# GPS.net
KiCad netlist of a schematic drawn in Altium Designer
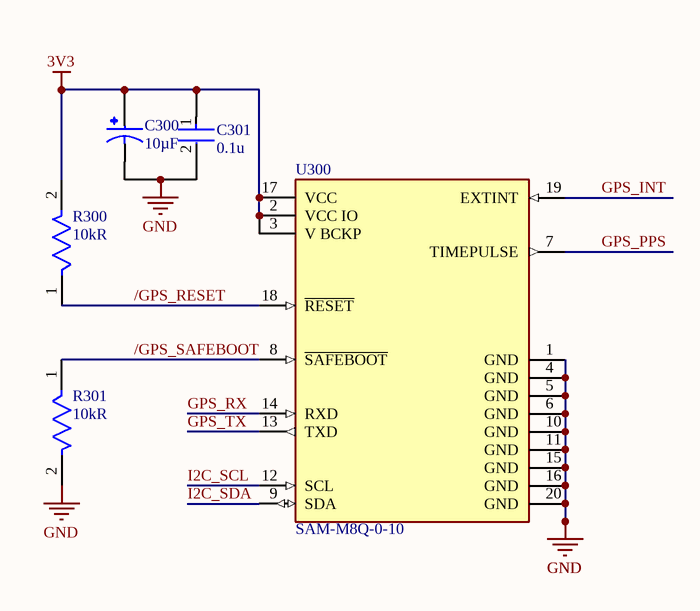
[diagram p0: GPS.SchDoc]

(export (version "E")
  (design (tool "Eeschema 10.0.6"))
  (components
    (comp (ref "C300")
      (value "10µF")
      (footprint "CAP_EEEFN1C100R")
      (description "10ÂµF 16V Aluminum Electrolytic Capacitors Radial, Can - SMD 1.35Ohm @ 100kHz 2000 Hrs @ 105Â°C")
      (fields (field (name "DIGI-KEY_PART_NUMBER") "10-EEE-FN1C100RCT-ND") (field (name "MP") "EEEFN1C100R"))
      (libsource (lib "Erich Robb") (part "EEEFN1C100R"))
    )
    (comp (ref "C301")
      (value "CL10C681JB8NFNC")
      (footprint "FP-CL10-IPC_A")
      (description "Cap Ceramic 680pF 50V C0G ±5% Pad SMD 0603 +125°C T/R")
      (fields (field (name "CAPACITANCE") "0.1u") (field (name "TOLERANCE") "5%"))
      (libsource (lib "Altium Content Vault") (part "b4654b650e69147ec39a6b967a45e02"))
    )
    (comp (ref "R300")
      (value "10kR")
      (footprint "FP-CPF0603-MFG")
      (description "RES SMD 2.15KΩ 0.1% 1/16W 0603")
      (fields
        (field (name "MANUFACTURER") "TE Connectivity")
        (field (name "OCTOPART") "https://octopart.com/cpf0603b2k15e1-te+connectivity-22739551")
      )
      (libsource (lib "Altium Content Vault") (part "1029c3af85768c4190bb7ad29bc67b5"))
    )
    (comp (ref "R301")
      (value "10kR")
      (footprint "FP-CPF0603-MFG")
      (description "RES SMD 2.15KΩ 0.1% 1/16W 0603")
      (fields
        (field (name "MANUFACTURER") "TE Connectivity")
        (field (name "OCTOPART") "https://octopart.com/cpf0603b2k15e1-te+connectivity-22739551")
      )
      (libsource (lib "Altium Content Vault") (part "1029c3af85768c4190bb7ad29bc67b5"))
    )
    (comp (ref "U300")
      (value "SAM-M8Q-0-10")
      (footprint "FP-SAM-M8Q-0-10-MFG")
      (description "RF RX GALILEO 1.575GHZ/1.602GHZ")
      (fields
        (field (name "MANUFACTURER") "uBlox")
        (field (name "OCTOPART") "https://octopart.com/sam-m8q-0-10-u-blox-88247750")
      )
      (libsource (lib "Altium Content Vault") (part "e897669bc61729ed63f6e62e0b1e840"))
    )
  )
  (nets
    (net (code "1") (name "/GPS_INT") (class "Default")
      (node (ref "U300") (pin "19") (pinfunction "EXTINT_19") (pintype "input"))
    )
    (net (code "2") (name "/GPS_PPS") (class "Default")
      (node (ref "U300") (pin "7") (pinfunction "TIMEPULSE_7") (pintype "output"))
    )
    (net (code "3") (name "/GPS_RX") (class "Default")
      (node (ref "U300") (pin "14") (pinfunction "RXD_14") (pintype "input"))
    )
    (net (code "4") (name "/GPS_TX") (class "Default")
      (node (ref "U300") (pin "13") (pinfunction "TXD_13") (pintype "output"))
    )
    (net (code "5") (name "/I2C_SCL") (class "Default")
      (node (ref "U300") (pin "12") (pinfunction "SCL_12") (pintype "input"))
    )
    (net (code "6") (name "/I2C_SDA") (class "Default")
      (node (ref "U300") (pin "9") (pinfunction "SDA_9") (pintype "bidirectional"))
    )
    (net (code "7") (name "/{slash}GPS_RESET") (class "Default")
      (node (ref "R300") (pin "1") (pinfunction "1_1") (pintype "passive"))
      (node (ref "U300") (pin "18") (pinfunction "~{RESET}_18") (pintype "input"))
    )
    (net (code "8") (name "/{slash}GPS_SAFEBOOT") (class "Default")
      (node (ref "R301") (pin "1") (pinfunction "1_1") (pintype "passive"))
      (node (ref "U300") (pin "8") (pinfunction "~{SAFEBOOT}_8") (pintype "input"))
    )
    (net (code "9") (name "3V3") (class "Default")
      (node (ref "C300") (pin "1") (pinfunction "1_1") (pintype "passive"))
      (node (ref "C301") (pin "1") (pinfunction "1_1") (pintype "passive"))
      (node (ref "R300") (pin "2") (pinfunction "2_2") (pintype "passive"))
      (node (ref "U300") (pin "17") (pinfunction "VCC_17") (pintype "power_in"))
      (node (ref "U300") (pin "2") (pinfunction "VCC_IO_2") (pintype "power_in"))
      (node (ref "U300") (pin "3") (pinfunction "V_BCKP_3") (pintype "power_in"))
    )
    (net (code "10") (name "GND") (class "Default")
      (node (ref "C300") (pin "2") (pinfunction "2_2") (pintype "passive"))
      (node (ref "C301") (pin "2") (pinfunction "2_2") (pintype "passive"))
      (node (ref "R301") (pin "2") (pinfunction "2_2") (pintype "passive"))
      (node (ref "U300") (pin "1") (pinfunction "GND_1") (pintype "power_in"))
      (node (ref "U300") (pin "10") (pinfunction "GND_10") (pintype "power_in"))
      (node (ref "U300") (pin "11") (pinfunction "GND_11") (pintype "power_in"))
      (node (ref "U300") (pin "15") (pinfunction "GND_15") (pintype "power_in"))
      (node (ref "U300") (pin "16") (pinfunction "GND_16") (pintype "power_in"))
      (node (ref "U300") (pin "20") (pinfunction "GND_20") (pintype "power_in"))
      (node (ref "U300") (pin "4") (pinfunction "GND_4") (pintype "power_in"))
      (node (ref "U300") (pin "5") (pinfunction "GND_5") (pintype "power_in"))
      (node (ref "U300") (pin "6") (pinfunction "GND_6") (pintype "power_in"))
    )
  )
)
